# lochitron_esp.net
KiCad netlist of a schematic drawn in EAGLE
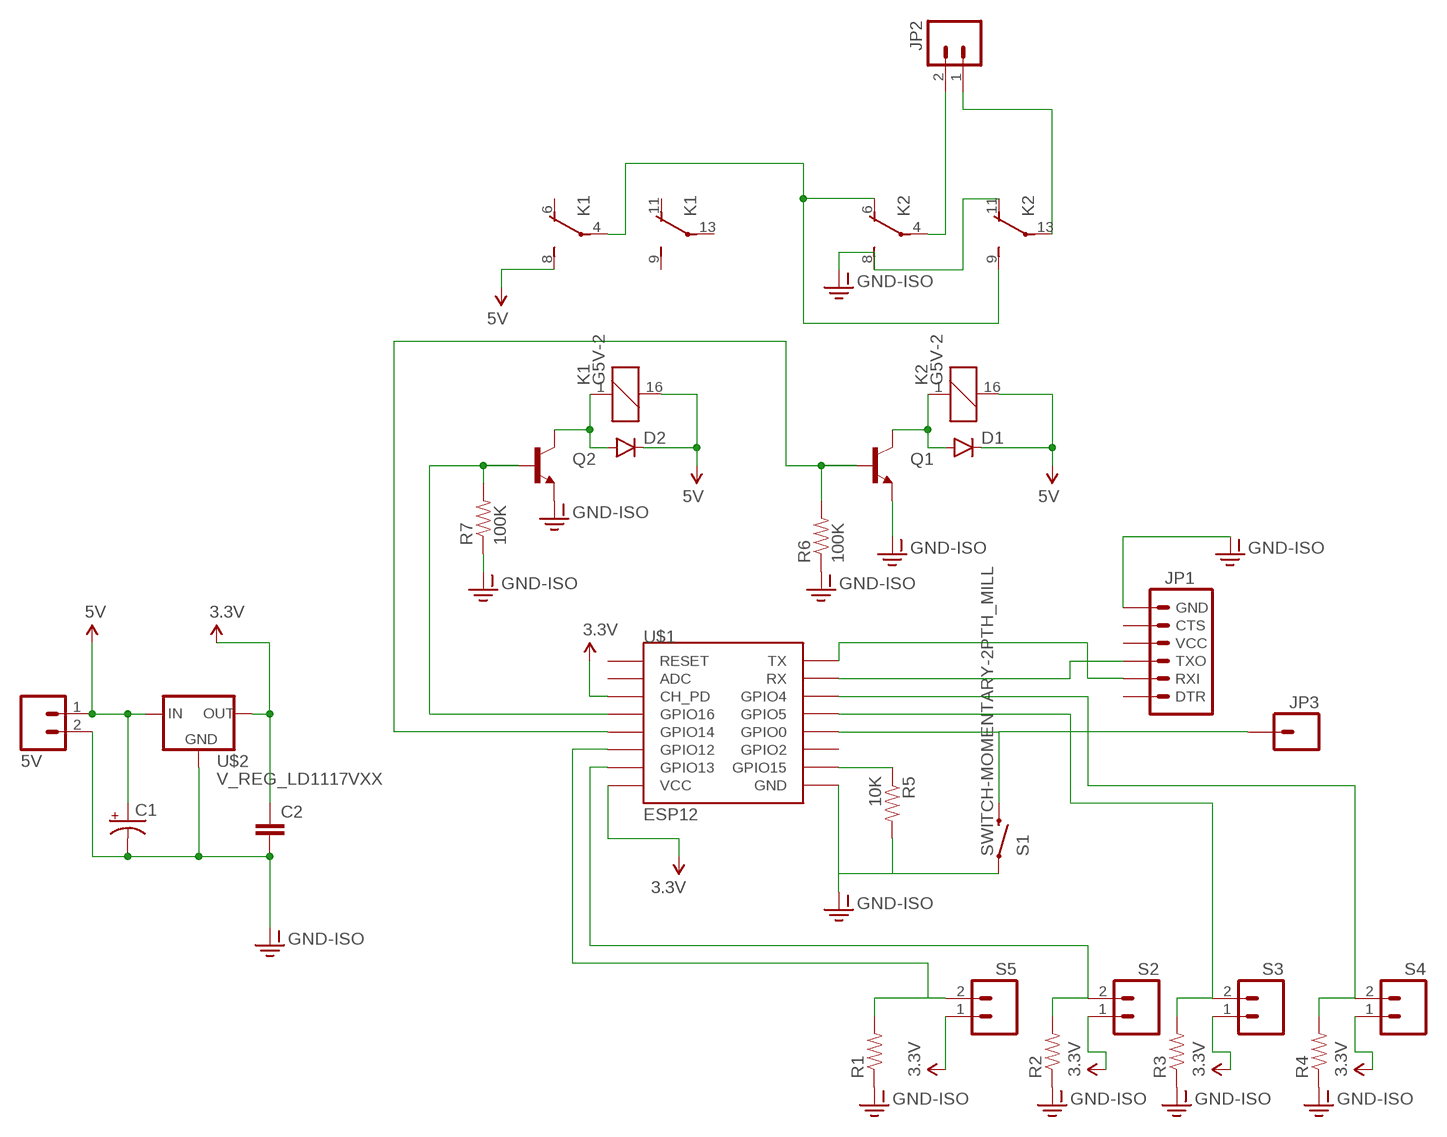
[diagram p0: schematic, sheet 1]

(export (version "E")
  (design (tool "Eeschema 10.0.6"))
  (components
    (comp (ref "5V")
      (value "M02LOCK_LONGPADS")
      (footprint "eagle-import:1X02_LOCK_LONGPADS")
      (libsource (lib "eagle-import") (part "M02LOCK_LONGPADS"))
    )
    (comp (ref "C1")
      (value "100UF-25V-20%(PTH)")
      (footprint "eagle-import:CPOL-RADIAL-100UF-25V")
      (libsource (lib "eagle-import") (part "100UF-25V-20%(PTH)"))
    )
    (comp (ref "C2")
      (value "0.1UF-50V-20%(PTH)KIT-EZ")
      (footprint "eagle-import:CAP-PTH-SMALL-KIT")
      (libsource (lib "eagle-import") (part "0.1UF-50V-20%(PTH)KIT-EZ"))
    )
    (comp (ref "D1")
      (value "DIODE1N4148")
      (footprint "eagle-import:DIODE-1N4148")
      (libsource (lib "eagle-import") (part "DIODE1N4148"))
    )
    (comp (ref "D2")
      (value "DIODE1N4148")
      (footprint "eagle-import:DIODE-1N4148")
      (libsource (lib "eagle-import") (part "DIODE1N4148"))
    )
    (comp (ref "JP1")
      (value "ARDUINO_SERIAL_PROGRAMLONGPADS")
      (footprint "eagle-import:1X06_LONGPADS")
      (libsource (lib "eagle-import") (part "ARDUINO_SERIAL_PROGRAMLONGPADS"))
    )
    (comp (ref "JP2")
      (value "M02LOCK_LONGPADS")
      (footprint "eagle-import:1X02_LOCK_LONGPADS")
      (libsource (lib "eagle-import") (part "M02LOCK_LONGPADS"))
    )
    (comp (ref "JP3")
      (value "M01PTH_LONGPAD")
      (footprint "eagle-import:1X01_LONGPAD")
      (libsource (lib "eagle-import") (part "M01PTH_LONGPAD"))
    )
    (comp (ref "K1")
      (value "G5V-2")
      (footprint "eagle-import:G5V-2")
      (fields (field (name "MPN") "G5V-2 5DC"))
      (libsource (lib "eagle-import") (part "G5V-2"))
    )
    (comp (ref "K2")
      (value "G5V-2")
      (footprint "eagle-import:G5V-2")
      (fields (field (name "MPN") "G5V-2 5DC"))
      (libsource (lib "eagle-import") (part "G5V-2"))
    )
    (comp (ref "Q1")
      (value "TRANSISTOR_NPNBC547")
      (footprint "eagle-import:TO-92-AMMO")
      (libsource (lib "eagle-import") (part "TRANSISTOR_NPNBC547"))
    )
    (comp (ref "Q2")
      (value "TRANSISTOR_NPNBC547")
      (footprint "eagle-import:TO-92-AMMO")
      (libsource (lib "eagle-import") (part "TRANSISTOR_NPNBC547"))
    )
    (comp (ref "R1")
      (value "RESISTORAXIAL-0.3")
      (footprint "eagle-import:AXIAL-0.3")
      (libsource (lib "eagle-import") (part "RESISTORAXIAL-0.3"))
    )
    (comp (ref "R2")
      (value "RESISTORAXIAL-0.3")
      (footprint "eagle-import:AXIAL-0.3")
      (libsource (lib "eagle-import") (part "RESISTORAXIAL-0.3"))
    )
    (comp (ref "R3")
      (value "RESISTORAXIAL-0.3")
      (footprint "eagle-import:AXIAL-0.3")
      (libsource (lib "eagle-import") (part "RESISTORAXIAL-0.3"))
    )
    (comp (ref "R4")
      (value "RESISTORAXIAL-0.3")
      (footprint "eagle-import:AXIAL-0.3")
      (libsource (lib "eagle-import") (part "RESISTORAXIAL-0.3"))
    )
    (comp (ref "R5")
      (value "10K")
      (footprint "eagle-import:AXIAL-0.3")
      (libsource (lib "eagle-import") (part "RESISTORAXIAL-0.3"))
    )
    (comp (ref "R6")
      (value "100K")
      (footprint "eagle-import:AXIAL-0.3")
      (libsource (lib "eagle-import") (part "100KOHM-1/4W-1%(PTH)HORIZ"))
    )
    (comp (ref "R7")
      (value "100K")
      (footprint "eagle-import:AXIAL-0.3")
      (libsource (lib "eagle-import") (part "100KOHM-1/4W-1%(PTH)HORIZ"))
    )
    (comp (ref "S1")
      (value "SWITCH-MOMENTARY-2PTH_MILL")
      (footprint "eagle-import:TACTILE-PTH")
      (libsource (lib "eagle-import") (part "SWITCH-MOMENTARY-2PTH_MILL"))
    )
    (comp (ref "S2")
      (value "M02LOCK_LONGPADS")
      (footprint "eagle-import:1X02_LOCK_LONGPADS")
      (libsource (lib "eagle-import") (part "M02LOCK_LONGPADS"))
    )
    (comp (ref "S3")
      (value "M02LOCK_LONGPADS")
      (footprint "eagle-import:1X02_LOCK_LONGPADS")
      (libsource (lib "eagle-import") (part "M02LOCK_LONGPADS"))
    )
    (comp (ref "S4")
      (value "M02LOCK_LONGPADS")
      (footprint "eagle-import:1X02_LOCK_LONGPADS")
      (libsource (lib "eagle-import") (part "M02LOCK_LONGPADS"))
    )
    (comp (ref "S5")
      (value "M02LOCK_LONGPADS")
      (footprint "eagle-import:1X02_LOCK_LONGPADS")
      (libsource (lib "eagle-import") (part "M02LOCK_LONGPADS"))
    )
    (comp (ref "U$1")
      (value "ESP12")
      (footprint "eagle-import:ESP12")
      (libsource (lib "eagle-import") (part "ESP12"))
    )
    (comp (ref "U$2")
      (value "V_REG_LD1117VXX")
      (footprint "eagle-import:78XXL")
      (libsource (lib "eagle-import") (part "V_REG_LD1117VXX"))
    )
  )
  (nets
    (net (code "1") (name "3.3V") (class "Default")
      (node (ref "C2") (pin "1") (pinfunction "1_1") (pintype "passive"))
      (node (ref "S2") (pin "1") (pinfunction "1_1") (pintype "passive"))
      (node (ref "S3") (pin "1") (pinfunction "1_1") (pintype "passive"))
      (node (ref "S4") (pin "1") (pinfunction "1_1") (pintype "passive"))
      (node (ref "S5") (pin "1") (pinfunction "1_1") (pintype "passive"))
      (node (ref "U$1") (pin "CH_PD") (pinfunction "CH_PD_CH_PD") (pintype "bidirectional"))
      (node (ref "U$1") (pin "VCC") (pinfunction "VCC_VCC") (pintype "bidirectional"))
      (node (ref "U$2") (pin "GND") (pinfunction "OUT_GND") (pintype "passive"))
    )
    (net (code "2") (name "5V") (class "Default")
      (node (ref "5V") (pin "1") (pinfunction "1_1") (pintype "passive"))
      (node (ref "C1") (pin "1") (pinfunction "+_1") (pintype "passive"))
      (node (ref "D1") (pin "C") (pinfunction "C_C") (pintype "passive"))
      (node (ref "D2") (pin "C") (pinfunction "C_C") (pintype "passive"))
      (node (ref "K1") (pin "16") (pinfunction "2_16") (pintype "passive"))
      (node (ref "K1") (pin "8") (pinfunction "S_8") (pintype "passive"))
      (node (ref "K2") (pin "16") (pinfunction "2_16") (pintype "passive"))
      (node (ref "U$2") (pin "OUT") (pinfunction "IN_OUT") (pintype "input"))
    )
    (net (code "3") (name "GND-ISO") (class "Default")
      (node (ref "5V") (pin "2") (pinfunction "2_2") (pintype "passive"))
      (node (ref "C1") (pin "2") (pinfunction "-_2") (pintype "passive"))
      (node (ref "C2") (pin "2") (pinfunction "2_2") (pintype "passive"))
      (node (ref "JP1") (pin "6") (pinfunction "GND_6") (pintype "passive"))
      (node (ref "K2") (pin "11") (pinfunction "O_11") (pintype "passive"))
      (node (ref "K2") (pin "8") (pinfunction "S_8") (pintype "passive"))
      (node (ref "Q1") (pin "3") (pinfunction "E_3") (pintype "passive"))
      (node (ref "Q2") (pin "3") (pinfunction "E_3") (pintype "passive"))
      (node (ref "R1") (pin "P$1") (pinfunction "1_P$1") (pintype "passive"))
      (node (ref "R2") (pin "P$1") (pinfunction "1_P$1") (pintype "passive"))
      (node (ref "R3") (pin "P$1") (pinfunction "1_P$1") (pintype "passive"))
      (node (ref "R4") (pin "P$1") (pinfunction "1_P$1") (pintype "passive"))
      (node (ref "R5") (pin "P$2") (pinfunction "2_P$2") (pintype "passive"))
      (node (ref "R6") (pin "P$1") (pinfunction "1_P$1") (pintype "passive"))
      (node (ref "R7") (pin "P$1") (pinfunction "1_P$1") (pintype "passive"))
      (node (ref "S1") (pin "1") (pinfunction "1_1") (pintype "passive"))
      (node (ref "U$1") (pin "GND") (pinfunction "GND_GND") (pintype "bidirectional"))
      (node (ref "U$2") (pin "IN") (pinfunction "GND_IN") (pintype "input"))
    )
    (net (code "4") (name "Net-(JP1-RXI)") (class "Default")
      (node (ref "JP1") (pin "2") (pinfunction "RXI_2") (pintype "passive"))
      (node (ref "U$1") (pin "TX") (pinfunction "TX_TX") (pintype "bidirectional"))
    )
    (net (code "5") (name "Net-(JP1-TXO)") (class "Default")
      (node (ref "JP1") (pin "3") (pinfunction "TXO_3") (pintype "passive"))
      (node (ref "U$1") (pin "RX") (pinfunction "RX_RX") (pintype "bidirectional"))
    )
    (net (code "6") (name "Net-(K1A-P)") (class "Default")
      (node (ref "K1") (pin "4") (pinfunction "P_4") (pintype "passive"))
      (node (ref "K2") (pin "6") (pinfunction "O_6") (pintype "passive"))
      (node (ref "K2") (pin "9") (pinfunction "S_9") (pintype "passive"))
    )
    (net (code "7") (name "Net-(K2A-P)") (class "Default")
      (node (ref "JP2") (pin "2") (pinfunction "2_2") (pintype "passive"))
      (node (ref "K2") (pin "4") (pinfunction "P_4") (pintype "passive"))
    )
    (net (code "8") (name "Net-(K2B-P)") (class "Default")
      (node (ref "JP2") (pin "1") (pinfunction "1_1") (pintype "passive"))
      (node (ref "K2") (pin "13") (pinfunction "P_13") (pintype "passive"))
    )
    (net (code "9") (name "Net-(Q1-B)") (class "Default")
      (node (ref "Q1") (pin "2") (pinfunction "B_2") (pintype "passive"))
      (node (ref "R6") (pin "P$2") (pinfunction "2_P$2") (pintype "passive"))
      (node (ref "U$1") (pin "GPIO14") (pinfunction "GPIO14_GPIO14") (pintype "bidirectional"))
    )
    (net (code "10") (name "Net-(Q1-C)") (class "Default")
      (node (ref "D1") (pin "A") (pinfunction "A_A") (pintype "passive"))
      (node (ref "K2") (pin "1") (pinfunction "1_1") (pintype "passive"))
      (node (ref "Q1") (pin "1") (pinfunction "C_1") (pintype "passive"))
    )
    (net (code "11") (name "Net-(Q2-B)") (class "Default")
      (node (ref "Q2") (pin "2") (pinfunction "B_2") (pintype "passive"))
      (node (ref "R7") (pin "P$2") (pinfunction "2_P$2") (pintype "passive"))
      (node (ref "U$1") (pin "GPIO16") (pinfunction "GPIO16_GPIO16") (pintype "bidirectional"))
    )
    (net (code "12") (name "Net-(Q2-C)") (class "Default")
      (node (ref "D2") (pin "A") (pinfunction "A_A") (pintype "passive"))
      (node (ref "K1") (pin "1") (pinfunction "1_1") (pintype "passive"))
      (node (ref "Q2") (pin "1") (pinfunction "C_1") (pintype "passive"))
    )
    (net (code "13") (name "Net-(R1-2)") (class "Default")
      (node (ref "R1") (pin "P$2") (pinfunction "2_P$2") (pintype "passive"))
      (node (ref "S5") (pin "2") (pinfunction "2_2") (pintype "passive"))
      (node (ref "U$1") (pin "GPIO12") (pinfunction "GPIO12_GPIO12") (pintype "bidirectional"))
    )
    (net (code "14") (name "Net-(R2-2)") (class "Default")
      (node (ref "R2") (pin "P$2") (pinfunction "2_P$2") (pintype "passive"))
      (node (ref "S2") (pin "2") (pinfunction "2_2") (pintype "passive"))
      (node (ref "U$1") (pin "GPIO13") (pinfunction "GPIO13_GPIO13") (pintype "bidirectional"))
    )
    (net (code "15") (name "Net-(R3-2)") (class "Default")
      (node (ref "R3") (pin "P$2") (pinfunction "2_P$2") (pintype "passive"))
      (node (ref "S3") (pin "2") (pinfunction "2_2") (pintype "passive"))
      (node (ref "U$1") (pin "GPIO5") (pinfunction "GPIO5_GPIO5") (pintype "bidirectional"))
    )
    (net (code "16") (name "Net-(R4-2)") (class "Default")
      (node (ref "R4") (pin "P$2") (pinfunction "2_P$2") (pintype "passive"))
      (node (ref "S4") (pin "2") (pinfunction "2_2") (pintype "passive"))
      (node (ref "U$1") (pin "GPIO4") (pinfunction "GPIO4_GPIO4") (pintype "bidirectional"))
    )
    (net (code "17") (name "Net-(R5-1)") (class "Default")
      (node (ref "R5") (pin "P$1") (pinfunction "1_P$1") (pintype "passive"))
      (node (ref "U$1") (pin "GPIO15") (pinfunction "GPIO15_GPIO15") (pintype "bidirectional"))
    )
    (net (code "18") (name "Net-(S1-2)") (class "Default")
      (node (ref "JP3") (pin "1") (pinfunction "1_1") (pintype "passive"))
      (node (ref "S1") (pin "3") (pinfunction "2_3") (pintype "passive"))
      (node (ref "U$1") (pin "GPIO0") (pinfunction "GPIO0_GPIO0") (pintype "bidirectional"))
    )
    (net (code "19") (name "unconnected-(JP1-CTS-Pad5)") (class "Default")
      (node (ref "JP1") (pin "5") (pinfunction "CTS_5") (pintype "passive"))
    )
    (net (code "20") (name "unconnected-(JP1-DTR-Pad1)") (class "Default")
      (node (ref "JP1") (pin "1") (pinfunction "DTR_1") (pintype "passive"))
    )
    (net (code "21") (name "unconnected-(JP1-VCC-Pad4)") (class "Default")
      (node (ref "JP1") (pin "4") (pinfunction "VCC_4") (pintype "passive"))
    )
    (net (code "22") (name "unconnected-(K1A-O-Pad6)") (class "Default")
      (node (ref "K1") (pin "6") (pinfunction "O_6") (pintype "passive"))
    )
    (net (code "23") (name "unconnected-(K1B-O-Pad11)") (class "Default")
      (node (ref "K1") (pin "11") (pinfunction "O_11") (pintype "passive"))
    )
    (net (code "24") (name "unconnected-(K1B-P-Pad13)") (class "Default")
      (node (ref "K1") (pin "13") (pinfunction "P_13") (pintype "passive"))
    )
    (net (code "25") (name "unconnected-(K1B-S-Pad9)") (class "Default")
      (node (ref "K1") (pin "9") (pinfunction "S_9") (pintype "passive"))
    )
    (net (code "26") (name "unconnected-(U$1-PadADC)") (class "Default")
      (node (ref "U$1") (pin "ADC") (pinfunction "ADC_ADC") (pintype "bidirectional"))
    )
    (net (code "27") (name "unconnected-(U$1-PadGPIO2)") (class "Default")
      (node (ref "U$1") (pin "GPIO2") (pinfunction "GPIO2_GPIO2") (pintype "bidirectional"))
    )
    (net (code "28") (name "unconnected-(U$1-PadRESET)") (class "Default")
      (node (ref "U$1") (pin "RESET") (pinfunction "RESET_RESET") (pintype "bidirectional"))
    )
  )
)
